# lan_board.net
KiCad netlist of a schematic drawn in Altium Designer
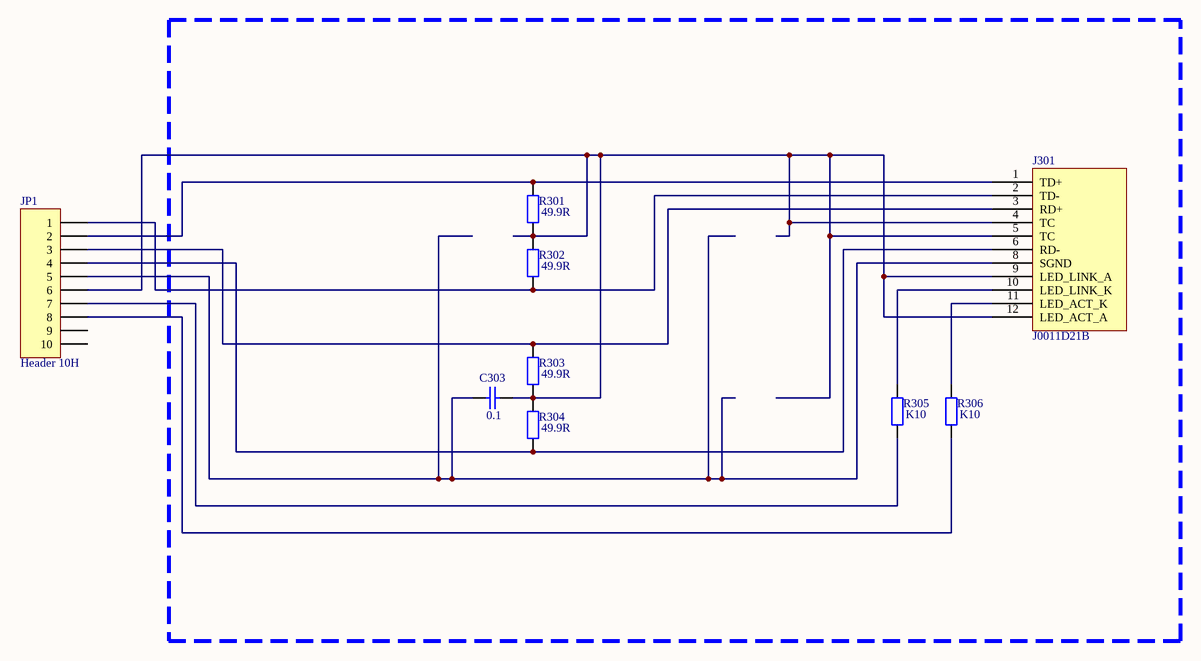
[diagram p0: lan_board.SchDoc]

(export (version "E")
  (design (tool "Eeschema 10.0.6"))
  (components
    (comp (ref "C303")
      (value "0.1")
      (footprint "C3216-1206")
      (description "Capacitor (Semiconductor SIM Model)")
      (fields (field (name "MANUFACTURER") "Generic Components") (field (name "PUBLISHER") "Altium Limited"))
      (libsource (lib "Miscellaneous Devices") (part "Cap Semi"))
    )
    (comp (ref "J301") (value "J0011D21B") (footprint "J0011D21B") (libsource (lib "PAL") (part "J0011D21B")))
    (comp (ref "JP1")
      (value "Header 10H")
      (footprint "HDR2X5")
      (description "Header, 10-Pin, Right Angle")
      (fields (field (name "MANUFACTURER") "Generic Components") (field (name "PUBLISHER") "Altium Limited"))
      (libsource (lib "Miscellaneous Connectors") (part "Header 10H"))
    )
    (comp (ref "R301")
      (value "49.9R")
      (footprint "_1206")
      (description "Resistor")
      (fields (field (name "MANUFACTURER") "Generic Components") (field (name "PUBLISHER") "Altium Limited"))
      (libsource (lib "Miscellaneous Devices") (part "Res2"))
    )
    (comp (ref "R302")
      (value "49.9R")
      (footprint "_1206")
      (description "Resistor")
      (fields (field (name "MANUFACTURER") "Generic Components") (field (name "PUBLISHER") "Altium Limited"))
      (libsource (lib "Miscellaneous Devices") (part "Res2"))
    )
    (comp (ref "R303")
      (value "49.9R")
      (footprint "_1206")
      (description "Resistor")
      (fields (field (name "MANUFACTURER") "Generic Components") (field (name "PUBLISHER") "Altium Limited"))
      (libsource (lib "Miscellaneous Devices") (part "Res2"))
    )
    (comp (ref "R304")
      (value "49.9R")
      (footprint "_1206")
      (description "Resistor")
      (fields (field (name "MANUFACTURER") "Generic Components") (field (name "PUBLISHER") "Altium Limited"))
      (libsource (lib "Miscellaneous Devices") (part "Res2"))
    )
    (comp (ref "R305")
      (value "K10")
      (footprint "_1206")
      (description "Resistor")
      (fields (field (name "MANUFACTURER") "Generic Components") (field (name "PUBLISHER") "Altium Limited"))
      (libsource (lib "Miscellaneous Devices") (part "Res2"))
    )
    (comp (ref "R306")
      (value "K10")
      (footprint "_1206")
      (description "Resistor")
      (fields (field (name "MANUFACTURER") "Generic Components") (field (name "PUBLISHER") "Altium Limited"))
      (libsource (lib "Miscellaneous Devices") (part "Res2"))
    )
  )
  (nets
    (net (code "1") (name "Net-(J301-LED_ACT_A)") (class "Default")
      (node (ref "C303") (pin "2") (pinfunction "2_2") (pintype "passive"))
      (node (ref "J301") (pin "12") (pinfunction "LED_ACT_A_12") (pintype "passive"))
      (node (ref "J301") (pin "4") (pinfunction "TC_4") (pintype "passive"))
      (node (ref "J301") (pin "5") (pinfunction "TC_5") (pintype "passive"))
      (node (ref "J301") (pin "9") (pinfunction "LED_LINK_A_9") (pintype "passive"))
      (node (ref "JP1") (pin "6") (pinfunction "6_6") (pintype "passive"))
      (node (ref "R301") (pin "2") (pinfunction "2_2") (pintype "passive"))
      (node (ref "R302") (pin "1") (pinfunction "1_1") (pintype "passive"))
      (node (ref "R303") (pin "2") (pinfunction "2_2") (pintype "passive"))
      (node (ref "R304") (pin "1") (pinfunction "1_1") (pintype "passive"))
    )
    (net (code "2") (name "Net-(J301-LED_ACT_K)") (class "Default")
      (node (ref "J301") (pin "11") (pinfunction "LED_ACT_K_11") (pintype "passive"))
      (node (ref "R306") (pin "1") (pinfunction "1_1") (pintype "passive"))
    )
    (net (code "3") (name "Net-(J301-LED_LINK_K)") (class "Default")
      (node (ref "J301") (pin "10") (pinfunction "LED_LINK_K_10") (pintype "passive"))
      (node (ref "R305") (pin "1") (pinfunction "1_1") (pintype "passive"))
    )
    (net (code "4") (name "Net-(J301-RD+)") (class "Default")
      (node (ref "J301") (pin "3") (pinfunction "RD+_3") (pintype "passive"))
      (node (ref "JP1") (pin "3") (pinfunction "3_3") (pintype "passive"))
      (node (ref "R303") (pin "1") (pinfunction "1_1") (pintype "passive"))
    )
    (net (code "5") (name "Net-(J301-RD-)") (class "Default")
      (node (ref "J301") (pin "6") (pinfunction "RD-_6") (pintype "passive"))
      (node (ref "JP1") (pin "4") (pinfunction "4_4") (pintype "passive"))
      (node (ref "R304") (pin "2") (pinfunction "2_2") (pintype "passive"))
    )
    (net (code "6") (name "Net-(J301-SGND)") (class "Default")
      (node (ref "C303") (pin "1") (pinfunction "1_1") (pintype "passive"))
      (node (ref "J301") (pin "8") (pinfunction "SGND_8") (pintype "passive"))
      (node (ref "JP1") (pin "5") (pinfunction "5_5") (pintype "passive"))
    )
    (net (code "7") (name "Net-(J301-TD+)") (class "Default")
      (node (ref "J301") (pin "1") (pinfunction "TD+_1") (pintype "passive"))
      (node (ref "JP1") (pin "2") (pinfunction "2_2") (pintype "passive"))
      (node (ref "R301") (pin "1") (pinfunction "1_1") (pintype "passive"))
    )
    (net (code "8") (name "Net-(J301-TD-)") (class "Default")
      (node (ref "J301") (pin "2") (pinfunction "TD-_2") (pintype "passive"))
      (node (ref "JP1") (pin "1") (pinfunction "1_1") (pintype "passive"))
      (node (ref "R302") (pin "2") (pinfunction "2_2") (pintype "passive"))
    )
    (net (code "9") (name "Net-(JP1-Pad7)") (class "Default")
      (node (ref "JP1") (pin "7") (pinfunction "7_7") (pintype "passive"))
      (node (ref "R305") (pin "2") (pinfunction "2_2") (pintype "passive"))
    )
    (net (code "10") (name "Net-(JP1-Pad8)") (class "Default")
      (node (ref "JP1") (pin "8") (pinfunction "8_8") (pintype "passive"))
      (node (ref "R306") (pin "2") (pinfunction "2_2") (pintype "passive"))
    )
    (net (code "11") (name "unconnected-(JP1-Pad9)") (class "Default")
      (node (ref "JP1") (pin "9") (pinfunction "9_9") (pintype "passive"))
    )
    (net (code "12") (name "unconnected-(JP1-Pad10)") (class "Default")
      (node (ref "JP1") (pin "10") (pinfunction "10_10") (pintype "passive"))
    )
  )
)
